# CW313_PCIe_Edge.net
KiCad netlist of a schematic drawn in Altium Designer
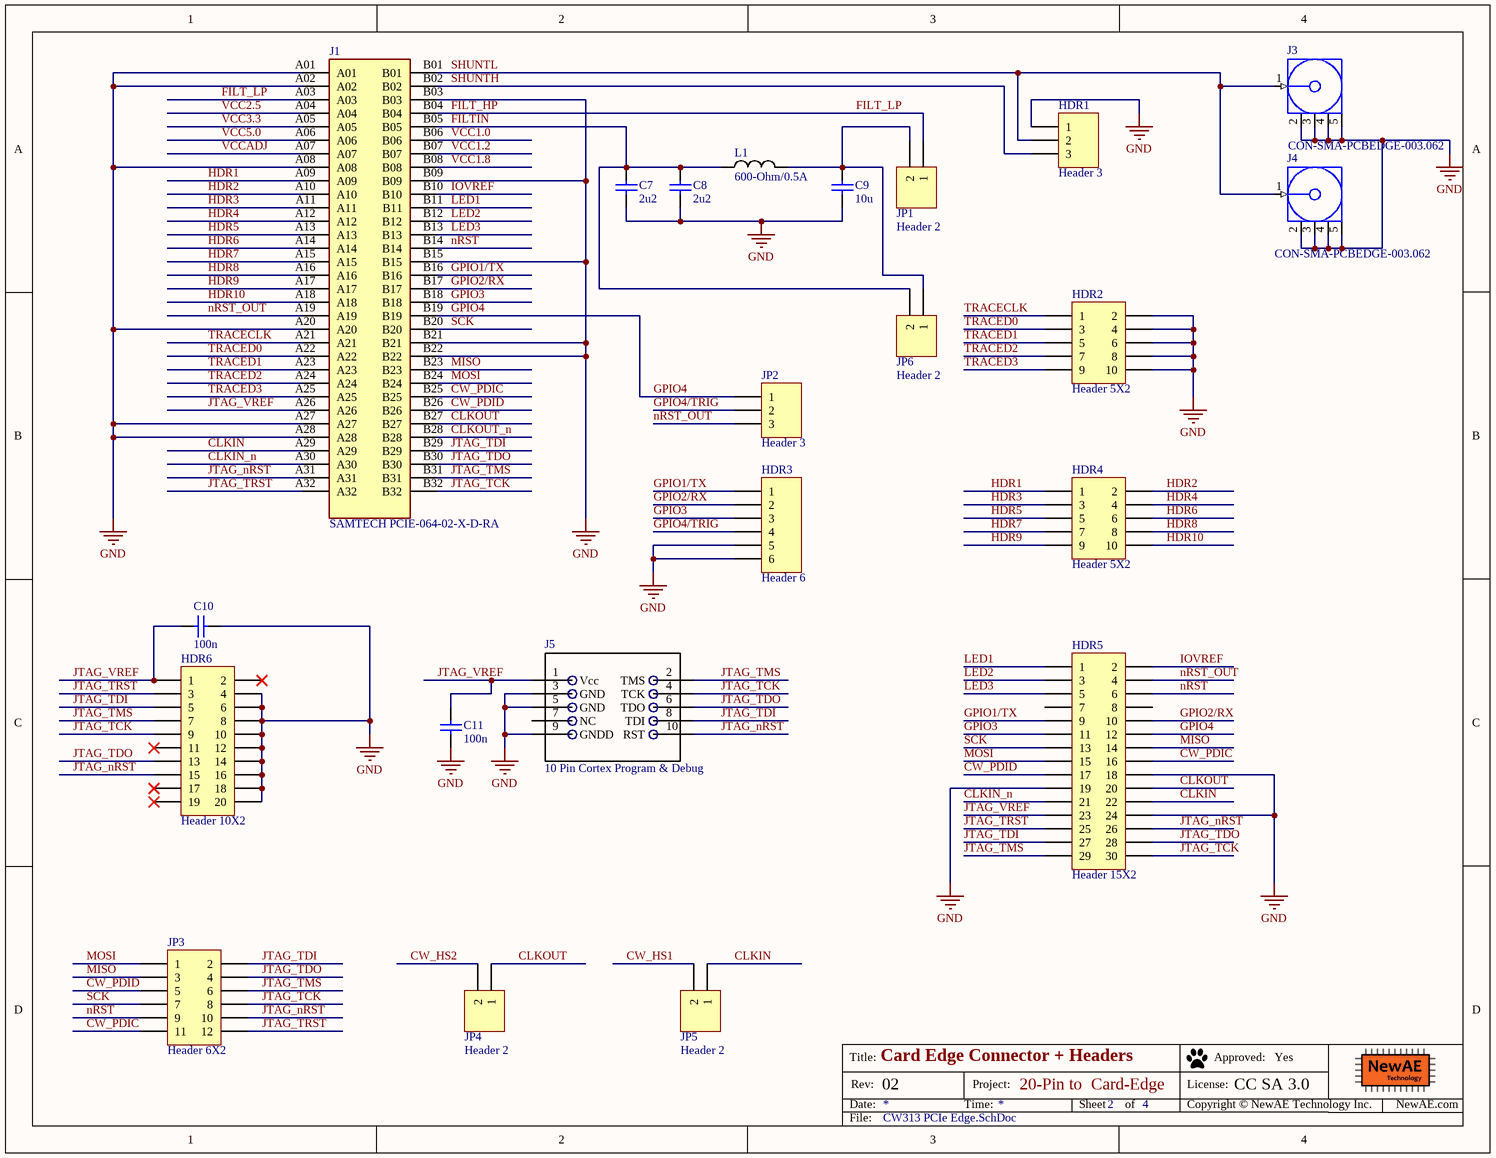
[diagram p0: CW313 PCIe Edge.SchDoc]

(export (version "E")
  (design (tool "Eeschema 10.0.6"))
  (components
    (comp (ref "C7")
      (value "2u2")
      (footprint "CAPC0603_M")
      (description "2u2, 0603")
      (fields (field (name "PART NUMBER") "CCHIP-2u2-0603-16V"))
      (libsource (lib "NewAE_AltiumLib") (part "CAP"))
    )
    (comp (ref "C8")
      (value "2u2")
      (footprint "CAPC0603_M")
      (description "2u2, 0603")
      (fields (field (name "PART NUMBER") "CCHIP-2u2-0603-16V"))
      (libsource (lib "NewAE_AltiumLib") (part "CAP"))
    )
    (comp (ref "C9")
      (value "10u")
      (footprint "CAPC1206_M")
      (description "CAP CER 10UF 25V X7R 1206")
      (fields (field (name "PART NUMBER") "CCHIP-10u-1206"))
      (libsource (lib "NewAE_AltiumLib") (part "CAP"))
    )
    (comp (ref "C10")
      (value "100n")
      (footprint "CAPC0603_M")
      (description "100n, 0603")
      (fields (field (name "PART NUMBER") "CCHIP-100n-0603"))
      (libsource (lib "NewAE_AltiumLib") (part "CAP"))
    )
    (comp (ref "C11")
      (value "100n")
      (footprint "CAPC0603_M")
      (description "100n, 0603")
      (fields (field (name "PART NUMBER") "CCHIP-100n-0603"))
      (libsource (lib "NewAE_AltiumLib") (part "CAP"))
    )
    (comp (ref "HDR1")
      (value "Header 3")
      (footprint "HDR1X3")
      (description "Header, 3-Pin")
      (fields (field (name "PUBLISHER") "Altium Limited"))
      (libsource (lib "Miscellaneous Connectors") (part "Header 3"))
    )
    (comp (ref "HDR2")
      (value "Header 5X2")
      (footprint "HDR2X5")
      (description "Header, 5-Pin, Dual row")
      (fields (field (name "PUBLISHER") "Altium Limited"))
      (libsource (lib "Miscellaneous Connectors") (part "Header 5X2"))
    )
    (comp (ref "HDR3")
      (value "Header 6")
      (footprint "HDR1X6")
      (description "Header, 6-Pin")
      (fields (field (name "PUBLISHER") "Altium Limited"))
      (libsource (lib "Miscellaneous Connectors") (part "Header 6"))
    )
    (comp (ref "HDR4")
      (value "Header 5X2")
      (footprint "HDR2X5")
      (description "Header, 5-Pin, Dual row")
      (fields (field (name "PUBLISHER") "Altium Limited"))
      (libsource (lib "Miscellaneous Connectors") (part "Header 5X2"))
    )
    (comp (ref "HDR5")
      (value "Header 15X2")
      (footprint "HDR2X15")
      (description "Header, 15-Pin, Dual row")
      (fields (field (name "PUBLISHER") "Altium Limited"))
      (libsource (lib "Miscellaneous Connectors") (part "Header 15X2"))
    )
    (comp (ref "HDR6")
      (value "Header 10X2")
      (footprint "HDR2X10")
      (description "Header, 10-Pin, Dual row")
      (fields (field (name "PUBLISHER") "Altium Limited"))
      (libsource (lib "Miscellaneous Connectors") (part "Header 10X2"))
    )
    (comp (ref "J1")
      (value "SAMTECH PCIE-064-02-X-D-RA")
      (footprint "SAMTEC_PCIE-064-02-X-D-RA")
      (description "1.00 mm PCI Express Edge Card Connector (Thick Gold)")
      (fields (field (name "MF") "Samtec") (field (name "MP") "PCIE-064-02-X-D-RA"))
      (libsource (lib "NewAE_AltiumLib") (part "PCIE-064-02-X-D-RA"))
    )
    (comp (ref "J3")
      (value "CON-SMA-PCBEDGE-003.062")
      (footprint "CON-SMAM-PCB-EDGE062")
      (description "SMA Female Edge Mount Connector for 0.062\" Thick Board")
      (libsource (lib "NewAE_AltiumLib") (part "CON-SMA-PCBEDGE-003.062"))
    )
    (comp (ref "J4")
      (value "CON-SMA-PCBEDGE-003.062")
      (footprint "CON-SMAM-PCB-EDGE062")
      (description "SMA Female Edge Mount Connector for 0.062\" Thick Board")
      (libsource (lib "NewAE_AltiumLib") (part "CON-SMA-PCBEDGE-003.062"))
    )
    (comp (ref "J5")
      (value "10 Pin Cortex Program & Debug")
      (footprint "0.5mm_SMD_Header_5x2")
      (description "10 Pin Cortex Program & Debug 0.5mm pitch")
      (fields (field (name "PART NUMBER") "Cortex_Debug_Header_10Pin"))
      (libsource (lib "NewAE_AltiumLib") (part "Cortex_Debug_Header_10Pin"))
    )
    (comp (ref "JP1")
      (value "Header 2")
      (footprint "HDR1X2")
      (description "Header, 2-Pin")
      (fields (field (name "PUBLISHER") "Altium Limited"))
      (libsource (lib "Miscellaneous Connectors") (part "Header 2"))
    )
    (comp (ref "JP2")
      (value "Header 3")
      (footprint "HDR1X3")
      (description "Header, 3-Pin")
      (fields (field (name "PUBLISHER") "Altium Limited"))
      (libsource (lib "Miscellaneous Connectors") (part "Header 3"))
    )
    (comp (ref "JP3")
      (value "Header 6X2")
      (footprint "HDR2X6")
      (description "Header, 6-Pin, Dual row")
      (fields (field (name "PUBLISHER") "Altium Limited"))
      (libsource (lib "Miscellaneous Connectors") (part "Header 6X2"))
    )
    (comp (ref "JP4")
      (value "Header 2")
      (footprint "HDR1X2")
      (description "Header, 2-Pin")
      (fields (field (name "PUBLISHER") "Altium Limited"))
      (libsource (lib "Miscellaneous Connectors") (part "Header 2"))
    )
    (comp (ref "JP5")
      (value "Header 2")
      (footprint "HDR1X2")
      (description "Header, 2-Pin")
      (fields (field (name "PUBLISHER") "Altium Limited"))
      (libsource (lib "Miscellaneous Connectors") (part "Header 2"))
    )
    (comp (ref "JP6")
      (value "Header 2")
      (footprint "HDR1X2")
      (description "Header, 2-Pin")
      (fields (field (name "PUBLISHER") "Altium Limited"))
      (libsource (lib "Miscellaneous Connectors") (part "Header 2"))
    )
    (comp (ref "L1")
      (value "600-Ohm/0.5A")
      (footprint "IND_0603")
      (description "600 Ohm @ 100 MHz, 0.5A rated FB")
      (fields (field (name "PART NUMBER") "FBCHIP-600R-0603"))
      (libsource (lib "NewAE_AltiumLib") (part "IND"))
    )
  )
  (nets
    (net (code "1") (name "/CLKIN") (class "Default")
      (node (ref "HDR5") (pin "22") (pinfunction "22_22") (pintype "passive"))
      (node (ref "J1") (pin "A29") (pinfunction "A29_A29") (pintype "passive"))
      (node (ref "JP5") (pin "1") (pinfunction "1_1") (pintype "passive"))
    )
    (net (code "2") (name "/CLKIN_n") (class "Default")
      (node (ref "HDR5") (pin "21") (pinfunction "21_21") (pintype "passive"))
      (node (ref "J1") (pin "A30") (pinfunction "A30_A30") (pintype "passive"))
    )
    (net (code "3") (name "/CLKOUT") (class "Default")
      (node (ref "HDR5") (pin "20") (pinfunction "20_20") (pintype "passive"))
      (node (ref "J1") (pin "B27") (pinfunction "B27_B27") (pintype "passive"))
      (node (ref "JP4") (pin "1") (pinfunction "1_1") (pintype "passive"))
    )
    (net (code "4") (name "/CLKOUT_n") (class "Default")
      (node (ref "J1") (pin "B28") (pinfunction "B28_B28") (pintype "passive"))
    )
    (net (code "5") (name "/CW_HS1") (class "Default")
      (node (ref "JP5") (pin "2") (pinfunction "2_2") (pintype "passive"))
    )
    (net (code "6") (name "/CW_HS2") (class "Default")
      (node (ref "JP4") (pin "2") (pinfunction "2_2") (pintype "passive"))
    )
    (net (code "7") (name "/CW_PDIC") (class "Default")
      (node (ref "HDR5") (pin "16") (pinfunction "16_16") (pintype "passive"))
      (node (ref "J1") (pin "B25") (pinfunction "B25_B25") (pintype "passive"))
      (node (ref "JP3") (pin "11") (pinfunction "11_11") (pintype "passive"))
    )
    (net (code "8") (name "/CW_PDID") (class "Default")
      (node (ref "HDR5") (pin "17") (pinfunction "17_17") (pintype "passive"))
      (node (ref "J1") (pin "B26") (pinfunction "B26_B26") (pintype "passive"))
      (node (ref "JP3") (pin "5") (pinfunction "5_5") (pintype "passive"))
    )
    (net (code "9") (name "/FILTIN") (class "Default")
      (node (ref "C7") (pin "1") (pinfunction "1_1") (pintype "passive"))
      (node (ref "C8") (pin "1") (pinfunction "1_1") (pintype "passive"))
      (node (ref "J1") (pin "B05") (pinfunction "B05_B05") (pintype "passive"))
      (node (ref "JP6") (pin "2") (pinfunction "2_2") (pintype "passive"))
      (node (ref "L1") (pin "1") (pinfunction "1_1") (pintype "passive"))
    )
    (net (code "10") (name "/FILT_HP") (class "Default")
      (node (ref "J1") (pin "A03") (pinfunction "A03_A03") (pintype "passive"))
      (node (ref "J1") (pin "B04") (pinfunction "B04_B04") (pintype "passive"))
      (node (ref "JP1") (pin "1") (pinfunction "1_1") (pintype "passive"))
    )
    (net (code "11") (name "/GPIO1{slash}TX") (class "Default")
      (node (ref "HDR3") (pin "1") (pinfunction "1_1") (pintype "passive"))
      (node (ref "HDR5") (pin "9") (pinfunction "9_9") (pintype "passive"))
      (node (ref "J1") (pin "B16") (pinfunction "B16_B16") (pintype "passive"))
    )
    (net (code "12") (name "/GPIO2{slash}RX") (class "Default")
      (node (ref "HDR3") (pin "2") (pinfunction "2_2") (pintype "passive"))
      (node (ref "HDR5") (pin "10") (pinfunction "10_10") (pintype "passive"))
      (node (ref "J1") (pin "B17") (pinfunction "B17_B17") (pintype "passive"))
    )
    (net (code "13") (name "/GPIO3") (class "Default")
      (node (ref "HDR3") (pin "3") (pinfunction "3_3") (pintype "passive"))
      (node (ref "HDR5") (pin "11") (pinfunction "11_11") (pintype "passive"))
      (node (ref "J1") (pin "B18") (pinfunction "B18_B18") (pintype "passive"))
    )
    (net (code "14") (name "/GPIO4") (class "Default")
      (node (ref "HDR5") (pin "12") (pinfunction "12_12") (pintype "passive"))
      (node (ref "J1") (pin "B19") (pinfunction "B19_B19") (pintype "passive"))
      (node (ref "JP2") (pin "1") (pinfunction "1_1") (pintype "passive"))
    )
    (net (code "15") (name "/GPIO4{slash}TRIG") (class "Default")
      (node (ref "HDR3") (pin "4") (pinfunction "4_4") (pintype "passive"))
      (node (ref "JP2") (pin "2") (pinfunction "2_2") (pintype "passive"))
    )
    (net (code "16") (name "/HDR1") (class "Default")
      (node (ref "HDR4") (pin "1") (pinfunction "1_1") (pintype "passive"))
      (node (ref "J1") (pin "A09") (pinfunction "A09_A09") (pintype "passive"))
    )
    (net (code "17") (name "/HDR2") (class "Default")
      (node (ref "HDR4") (pin "2") (pinfunction "2_2") (pintype "passive"))
      (node (ref "J1") (pin "A10") (pinfunction "A10_A10") (pintype "passive"))
    )
    (net (code "18") (name "/HDR3") (class "Default")
      (node (ref "HDR4") (pin "3") (pinfunction "3_3") (pintype "passive"))
      (node (ref "J1") (pin "A11") (pinfunction "A11_A11") (pintype "passive"))
    )
    (net (code "19") (name "/HDR4") (class "Default")
      (node (ref "HDR4") (pin "4") (pinfunction "4_4") (pintype "passive"))
      (node (ref "J1") (pin "A12") (pinfunction "A12_A12") (pintype "passive"))
    )
    (net (code "20") (name "/HDR5") (class "Default")
      (node (ref "HDR4") (pin "5") (pinfunction "5_5") (pintype "passive"))
      (node (ref "J1") (pin "A13") (pinfunction "A13_A13") (pintype "passive"))
    )
    (net (code "21") (name "/HDR6") (class "Default")
      (node (ref "HDR4") (pin "6") (pinfunction "6_6") (pintype "passive"))
      (node (ref "J1") (pin "A14") (pinfunction "A14_A14") (pintype "passive"))
    )
    (net (code "22") (name "/HDR7") (class "Default")
      (node (ref "HDR4") (pin "7") (pinfunction "7_7") (pintype "passive"))
      (node (ref "J1") (pin "A15") (pinfunction "A15_A15") (pintype "passive"))
    )
    (net (code "23") (name "/HDR8") (class "Default")
      (node (ref "HDR4") (pin "8") (pinfunction "8_8") (pintype "passive"))
      (node (ref "J1") (pin "A16") (pinfunction "A16_A16") (pintype "passive"))
    )
    (net (code "24") (name "/HDR9") (class "Default")
      (node (ref "HDR4") (pin "9") (pinfunction "9_9") (pintype "passive"))
      (node (ref "J1") (pin "A17") (pinfunction "A17_A17") (pintype "passive"))
    )
    (net (code "25") (name "/HDR10") (class "Default")
      (node (ref "HDR4") (pin "10") (pinfunction "10_10") (pintype "passive"))
      (node (ref "J1") (pin "A18") (pinfunction "A18_A18") (pintype "passive"))
    )
    (net (code "26") (name "/IOVREF") (class "Default")
      (node (ref "HDR5") (pin "2") (pinfunction "2_2") (pintype "passive"))
      (node (ref "J1") (pin "B10") (pinfunction "B10_B10") (pintype "passive"))
    )
    (net (code "27") (name "/JTAG_TCK") (class "Default")
      (node (ref "HDR5") (pin "30") (pinfunction "30_30") (pintype "passive"))
      (node (ref "HDR6") (pin "9") (pinfunction "9_9") (pintype "passive"))
      (node (ref "J1") (pin "B32") (pinfunction "B32_B32") (pintype "passive"))
      (node (ref "J5") (pin "4") (pinfunction "TCK_4") (pintype "passive"))
      (node (ref "JP3") (pin "8") (pinfunction "8_8") (pintype "passive"))
    )
    (net (code "28") (name "/JTAG_TDI") (class "Default")
      (node (ref "HDR5") (pin "27") (pinfunction "27_27") (pintype "passive"))
      (node (ref "HDR6") (pin "5") (pinfunction "5_5") (pintype "passive"))
      (node (ref "J1") (pin "B29") (pinfunction "B29_B29") (pintype "passive"))
      (node (ref "J5") (pin "8") (pinfunction "TDI_8") (pintype "passive"))
      (node (ref "JP3") (pin "2") (pinfunction "2_2") (pintype "passive"))
    )
    (net (code "29") (name "/JTAG_TDO") (class "Default")
      (node (ref "HDR5") (pin "28") (pinfunction "28_28") (pintype "passive"))
      (node (ref "HDR6") (pin "13") (pinfunction "13_13") (pintype "passive"))
      (node (ref "J1") (pin "B30") (pinfunction "B30_B30") (pintype "passive"))
      (node (ref "J5") (pin "6") (pinfunction "TDO_6") (pintype "passive"))
      (node (ref "JP3") (pin "4") (pinfunction "4_4") (pintype "passive"))
    )
    (net (code "30") (name "/JTAG_TMS") (class "Default")
      (node (ref "HDR5") (pin "29") (pinfunction "29_29") (pintype "passive"))
      (node (ref "HDR6") (pin "7") (pinfunction "7_7") (pintype "passive"))
      (node (ref "J1") (pin "B31") (pinfunction "B31_B31") (pintype "passive"))
      (node (ref "J5") (pin "2") (pinfunction "TMS_2") (pintype "passive"))
      (node (ref "JP3") (pin "6") (pinfunction "6_6") (pintype "passive"))
    )
    (net (code "31") (name "/JTAG_TRST") (class "Default")
      (node (ref "HDR5") (pin "25") (pinfunction "25_25") (pintype "passive"))
      (node (ref "HDR6") (pin "3") (pinfunction "3_3") (pintype "passive"))
      (node (ref "J1") (pin "A32") (pinfunction "A32_A32") (pintype "passive"))
      (node (ref "JP3") (pin "12") (pinfunction "12_12") (pintype "passive"))
    )
    (net (code "32") (name "/JTAG_VREF") (class "Default")
      (node (ref "C10") (pin "1") (pinfunction "1_1") (pintype "passive"))
      (node (ref "C11") (pin "1") (pinfunction "1_1") (pintype "passive"))
      (node (ref "HDR5") (pin "23") (pinfunction "23_23") (pintype "passive"))
      (node (ref "HDR6") (pin "1") (pinfunction "1_1") (pintype "passive"))
      (node (ref "J1") (pin "A26") (pinfunction "A26_A26") (pintype "passive"))
      (node (ref "J5") (pin "1") (pinfunction "Vcc_1") (pintype "passive"))
    )
    (net (code "33") (name "/JTAG_nRST") (class "Default")
      (node (ref "HDR5") (pin "26") (pinfunction "26_26") (pintype "passive"))
      (node (ref "HDR6") (pin "15") (pinfunction "15_15") (pintype "passive"))
      (node (ref "J1") (pin "A31") (pinfunction "A31_A31") (pintype "passive"))
      (node (ref "J5") (pin "10") (pinfunction "RST_10") (pintype "passive"))
      (node (ref "JP3") (pin "10") (pinfunction "10_10") (pintype "passive"))
    )
    (net (code "34") (name "/LED1") (class "Default")
      (node (ref "HDR5") (pin "1") (pinfunction "1_1") (pintype "passive"))
      (node (ref "J1") (pin "B11") (pinfunction "B11_B11") (pintype "passive"))
    )
    (net (code "35") (name "/LED2") (class "Default")
      (node (ref "HDR5") (pin "3") (pinfunction "3_3") (pintype "passive"))
      (node (ref "J1") (pin "B12") (pinfunction "B12_B12") (pintype "passive"))
    )
    (net (code "36") (name "/LED3") (class "Default")
      (node (ref "HDR5") (pin "5") (pinfunction "5_5") (pintype "passive"))
      (node (ref "J1") (pin "B13") (pinfunction "B13_B13") (pintype "passive"))
    )
    (net (code "37") (name "/MISO") (class "Default")
      (node (ref "HDR5") (pin "14") (pinfunction "14_14") (pintype "passive"))
      (node (ref "J1") (pin "B23") (pinfunction "B23_B23") (pintype "passive"))
      (node (ref "JP3") (pin "3") (pinfunction "3_3") (pintype "passive"))
    )
    (net (code "38") (name "/MOSI") (class "Default")
      (node (ref "HDR5") (pin "15") (pinfunction "15_15") (pintype "passive"))
      (node (ref "J1") (pin "B24") (pinfunction "B24_B24") (pintype "passive"))
      (node (ref "JP3") (pin "1") (pinfunction "1_1") (pintype "passive"))
    )
    (net (code "39") (name "/SCK") (class "Default")
      (node (ref "HDR5") (pin "13") (pinfunction "13_13") (pintype "passive"))
      (node (ref "J1") (pin "B20") (pinfunction "B20_B20") (pintype "passive"))
      (node (ref "JP3") (pin "7") (pinfunction "7_7") (pintype "passive"))
    )
    (net (code "40") (name "/SHUNTH") (class "Default")
      (node (ref "HDR1") (pin "3") (pinfunction "3_3") (pintype "passive"))
      (node (ref "J1") (pin "B02") (pinfunction "B02_B02") (pintype "passive"))
    )
    (net (code "41") (name "/SHUNTL") (class "Default")
      (node (ref "HDR1") (pin "2") (pinfunction "2_2") (pintype "passive"))
      (node (ref "J1") (pin "B01") (pinfunction "B01_B01") (pintype "passive"))
      (node (ref "J3") (pin "1") (pinfunction "Signal_1") (pintype "input"))
      (node (ref "J4") (pin "1") (pinfunction "Signal_1") (pintype "input"))
    )
    (net (code "42") (name "/TRACECLK") (class "Default")
      (node (ref "HDR2") (pin "1") (pinfunction "1_1") (pintype "passive"))
      (node (ref "J1") (pin "A21") (pinfunction "A21_A21") (pintype "passive"))
    )
    (net (code "43") (name "/TRACED0") (class "Default")
      (node (ref "HDR2") (pin "3") (pinfunction "3_3") (pintype "passive"))
      (node (ref "J1") (pin "A22") (pinfunction "A22_A22") (pintype "passive"))
    )
    (net (code "44") (name "/TRACED1") (class "Default")
      (node (ref "HDR2") (pin "5") (pinfunction "5_5") (pintype "passive"))
      (node (ref "J1") (pin "A23") (pinfunction "A23_A23") (pintype "passive"))
    )
    (net (code "45") (name "/TRACED2") (class "Default")
      (node (ref "HDR2") (pin "7") (pinfunction "7_7") (pintype "passive"))
      (node (ref "J1") (pin "A24") (pinfunction "A24_A24") (pintype "passive"))
    )
    (net (code "46") (name "/TRACED3") (class "Default")
      (node (ref "HDR2") (pin "9") (pinfunction "9_9") (pintype "passive"))
      (node (ref "J1") (pin "A25") (pinfunction "A25_A25") (pintype "passive"))
    )
    (net (code "47") (name "/VCC1.0") (class "Default")
      (node (ref "J1") (pin "B06") (pinfunction "B06_B06") (pintype "passive"))
    )
    (net (code "48") (name "/VCC1.2") (class "Default")
      (node (ref "J1") (pin "B07") (pinfunction "B07_B07") (pintype "passive"))
    )
    (net (code "49") (name "/VCC1.8") (class "Default")
      (node (ref "J1") (pin "B08") (pinfunction "B08_B08") (pintype "passive"))
    )
    (net (code "50") (name "/VCC2.5") (class "Default")
      (node (ref "J1") (pin "A04") (pinfunction "A04_A04") (pintype "passive"))
    )
    (net (code "51") (name "/VCC3.3") (class "Default")
      (node (ref "J1") (pin "A05") (pinfunction "A05_A05") (pintype "passive"))
    )
    (net (code "52") (name "/VCC5.0") (class "Default")
      (node (ref "J1") (pin "A06") (pinfunction "A06_A06") (pintype "passive"))
    )
    (net (code "53") (name "/VCCADJ") (class "Default")
      (node (ref "J1") (pin "A07") (pinfunction "A07_A07") (pintype "passive"))
    )
    (net (code "54") (name "/nRST") (class "Default")
      (node (ref "HDR5") (pin "6") (pinfunction "6_6") (pintype "passive"))
      (node (ref "J1") (pin "B14") (pinfunction "B14_B14") (pintype "passive"))
      (node (ref "JP3") (pin "9") (pinfunction "9_9") (pintype "passive"))
    )
    (net (code "55") (name "/nRST_OUT") (class "Default")
      (node (ref "HDR5") (pin "4") (pinfunction "4_4") (pintype "passive"))
      (node (ref "J1") (pin "A19") (pinfunction "A19_A19") (pintype "passive"))
      (node (ref "JP2") (pin "3") (pinfunction "3_3") (pintype "passive"))
    )
    (net (code "56") (name "GND") (class "Default")
      (node (ref "C10") (pin "2") (pinfunction "2_2") (pintype "passive"))
      (node (ref "C11") (pin "2") (pinfunction "2_2") (pintype "passive"))
      (node (ref "C7") (pin "2") (pinfunction "2_2") (pintype "passive"))
      (node (ref "C8") (pin "2") (pinfunction "2_2") (pintype "passive"))
      (node (ref "C9") (pin "2") (pinfunction "2_2") (pintype "passive"))
      (node (ref "HDR1") (pin "1") (pinfunction "1_1") (pintype "passive"))
      (node (ref "HDR2") (pin "10") (pinfunction "10_10") (pintype "passive"))
      (node (ref "HDR2") (pin "2") (pinfunction "2_2") (pintype "passive"))
      (node (ref "HDR2") (pin "4") (pinfunction "4_4") (pintype "passive"))
      (node (ref "HDR2") (pin "6") (pinfunction "6_6") (pintype "passive"))
      (node (ref "HDR2") (pin "8") (pinfunction "8_8") (pintype "passive"))
      (node (ref "HDR3") (pin "5") (pinfunction "5_5") (pintype "passive"))
      (node (ref "HDR3") (pin "6") (pinfunction "6_6") (pintype "passive"))
      (node (ref "HDR5") (pin "18") (pinfunction "18_18") (pintype "passive"))
      (node (ref "HDR5") (pin "19") (pinfunction "19_19") (pintype "passive"))
      (node (ref "HDR5") (pin "24") (pinfunction "24_24") (pintype "passive"))
      (node (ref "HDR6") (pin "10") (pinfunction "10_10") (pintype "passive"))
      (node (ref "HDR6") (pin "12") (pinfunction "12_12") (pintype "passive"))
      (node (ref "HDR6") (pin "14") (pinfunction "14_14") (pintype "passive"))
      (node (ref "HDR6") (pin "16") (pinfunction "16_16") (pintype "passive"))
      (node (ref "HDR6") (pin "18") (pinfunction "18_18") (pintype "passive"))
      (node (ref "HDR6") (pin "20") (pinfunction "20_20") (pintype "passive"))
      (node (ref "HDR6") (pin "4") (pinfunction "4_4") (pintype "passive"))
      (node (ref "HDR6") (pin "6") (pinfunction "6_6") (pintype "passive"))
      (node (ref "HDR6") (pin "8") (pinfunction "8_8") (pintype "passive"))
      (node (ref "J1") (pin "A01") (pinfunction "A01_A01") (pintype "passive"))
      (node (ref "J1") (pin "A02") (pinfunction "A02_A02") (pintype "passive"))
      (node (ref "J1") (pin "A08") (pinfunction "A08_A08") (pintype "passive"))
      (node (ref "J1") (pin "A20") (pinfunction "A20_A20") (pintype "passive"))
      (node (ref "J1") (pin "A27") (pinfunction "A27_A27") (pintype "passive"))
      (node (ref "J1") (pin "A28") (pinfunction "A28_A28") (pintype "passive"))
      (node (ref "J1") (pin "B03") (pinfunction "B03_B03") (pintype "passive"))
      (node (ref "J1") (pin "B09") (pinfunction "B09_B09") (pintype "passive"))
      (node (ref "J1") (pin "B15") (pinfunction "B15_B15") (pintype "passive"))
      (node (ref "J1") (pin "B21") (pinfunction "B21_B21") (pintype "passive"))
      (node (ref "J1") (pin "B22") (pinfunction "B22_B22") (pintype "passive"))
      (node (ref "J3") (pin "2") (pinfunction "GND_2") (pintype "power_in"))
      (node (ref "J3") (pin "3") (pinfunction "GND_3") (pintype "power_in"))
      (node (ref "J3") (pin "4") (pinfunction "GND_4") (pintype "power_in"))
      (node (ref "J3") (pin "5") (pinfunction "GND_5") (pintype "power_in"))
      (node (ref "J4") (pin "2") (pinfunction "GND_2") (pintype "power_in"))
      (node (ref "J4") (pin "3") (pinfunction "GND_3") (pintype "power_in"))
      (node (ref "J4") (pin "4") (pinfunction "GND_4") (pintype "power_in"))
      (node (ref "J4") (pin "5") (pinfunction "GND_5") (pintype "power_in"))
      (node (ref "J5") (pin "3") (pinfunction "GND_3") (pintype "passive"))
      (node (ref "J5") (pin "5") (pinfunction "GND_5") (pintype "passive"))
      (node (ref "J5") (pin "9") (pinfunction "GNDD_9") (pintype "passive"))
    )
    (net (code "57") (name "Net-(C9-Pad1)") (class "Default")
      (node (ref "C9") (pin "1") (pinfunction "1_1") (pintype "passive"))
      (node (ref "JP1") (pin "2") (pinfunction "2_2") (pintype "passive"))
      (node (ref "JP6") (pin "1") (pinfunction "1_1") (pintype "passive"))
      (node (ref "L1") (pin "2") (pinfunction "2_2") (pintype "passive"))
    )
    (net (code "58") (name "unconnected-(HDR5-Pad7)") (class "Default")
      (node (ref "HDR5") (pin "7") (pinfunction "7_7") (pintype "passive"))
    )
    (net (code "59") (name "unconnected-(HDR5-Pad8)") (class "Default")
      (node (ref "HDR5") (pin "8") (pinfunction "8_8") (pintype "passive"))
    )
    (net (code "60") (name "unconnected-(HDR6-Pad2)") (class "Default")
      (node (ref "HDR6") (pin "2") (pinfunction "2_2") (pintype "passive+no_connect"))
    )
    (net (code "61") (name "unconnected-(HDR6-Pad11)") (class "Default")
      (node (ref "HDR6") (pin "11") (pinfunction "11_11") (pintype "passive+no_connect"))
    )
    (net (code "62") (name "unconnected-(HDR6-Pad17)") (class "Default")
      (node (ref "HDR6") (pin "17") (pinfunction "17_17") (pintype "passive+no_connect"))
    )
    (net (code "63") (name "unconnected-(HDR6-Pad19)") (class "Default")
      (node (ref "HDR6") (pin "19") (pinfunction "19_19") (pintype "passive+no_connect"))
    )
    (net (code "64") (name "unconnected-(J5-NC-Pad7)") (class "Default")
      (node (ref "J5") (pin "7") (pinfunction "NC_7") (pintype "passive"))
    )
  )
)
